# rs232-4ch.net
KiCad netlist of a schematic drawn in Altium Designer
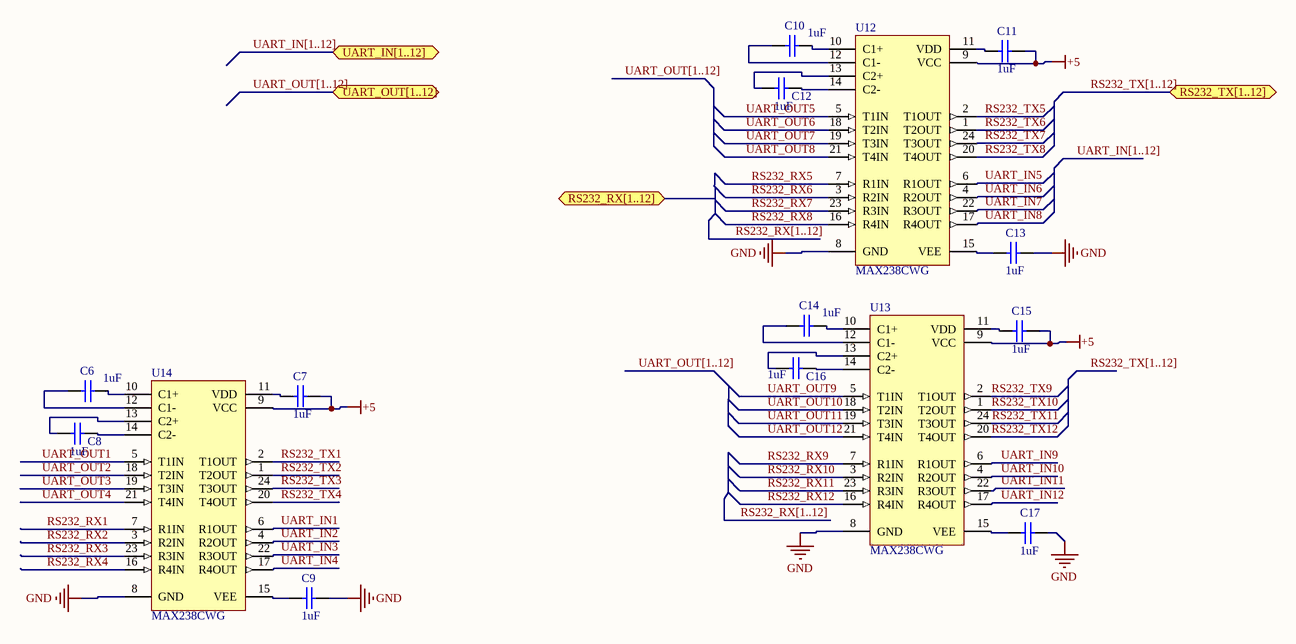
[diagram p0: rs232-4ch.SchDoc]

(export (version "E")
  (design (tool "Eeschema 10.0.6"))
  (components
    (comp (ref "C6")
      (value "1uF")
      (footprint "CAPC1608M")
      (description "Capacitor")
      (fields (field (name "Comment") "Cap") (field (name "PUBLISHER") "Altium Limited"))
      (libsource (lib "Miscellaneous Devices") (part "Cap"))
    )
    (comp (ref "C7")
      (value "1uF")
      (footprint "CAPC1608M")
      (description "Capacitor")
      (fields (field (name "Comment") "Cap") (field (name "PUBLISHER") "Altium Limited"))
      (libsource (lib "Miscellaneous Devices") (part "Cap"))
    )
    (comp (ref "C8")
      (value "1uF")
      (footprint "CAPC1608M")
      (description "Capacitor")
      (fields (field (name "Comment") "Cap") (field (name "PUBLISHER") "Altium Limited"))
      (libsource (lib "Miscellaneous Devices") (part "Cap"))
    )
    (comp (ref "C9")
      (value "1uF")
      (footprint "CAPC1608M")
      (description "Capacitor")
      (fields (field (name "Comment") "Cap") (field (name "PUBLISHER") "Altium Limited"))
      (libsource (lib "Miscellaneous Devices") (part "Cap"))
    )
    (comp (ref "C10")
      (value "1uF")
      (footprint "CAPC1608M")
      (description "Capacitor")
      (fields (field (name "Comment") "Cap") (field (name "PUBLISHER") "Altium Limited"))
      (libsource (lib "Miscellaneous Devices") (part "Cap"))
    )
    (comp (ref "C11")
      (value "1uF")
      (footprint "CAPC1608M")
      (description "Capacitor")
      (fields (field (name "Comment") "Cap") (field (name "PUBLISHER") "Altium Limited"))
      (libsource (lib "Miscellaneous Devices") (part "Cap"))
    )
    (comp (ref "C12")
      (value "1uF")
      (footprint "CAPC1608M")
      (description "Capacitor")
      (fields (field (name "Comment") "Cap") (field (name "PUBLISHER") "Altium Limited"))
      (libsource (lib "Miscellaneous Devices") (part "Cap"))
    )
    (comp (ref "C13")
      (value "1uF")
      (footprint "CAPC1608M")
      (description "Capacitor")
      (fields (field (name "Comment") "Cap") (field (name "PUBLISHER") "Altium Limited"))
      (libsource (lib "Miscellaneous Devices") (part "Cap"))
    )
    (comp (ref "C14")
      (value "1uF")
      (footprint "CAPC1608M")
      (description "Capacitor")
      (fields (field (name "Comment") "Cap") (field (name "PUBLISHER") "Altium Limited"))
      (libsource (lib "Miscellaneous Devices") (part "Cap"))
    )
    (comp (ref "C15")
      (value "1uF")
      (footprint "CAPC1608M")
      (description "Capacitor")
      (fields (field (name "Comment") "Cap") (field (name "PUBLISHER") "Altium Limited"))
      (libsource (lib "Miscellaneous Devices") (part "Cap"))
    )
    (comp (ref "C16")
      (value "1uF")
      (footprint "CAPC1608M")
      (description "Capacitor")
      (fields (field (name "Comment") "Cap") (field (name "PUBLISHER") "Altium Limited"))
      (libsource (lib "Miscellaneous Devices") (part "Cap"))
    )
    (comp (ref "C17")
      (value "1uF")
      (footprint "CAPC1608M")
      (description "Capacitor")
      (fields (field (name "Comment") "Cap") (field (name "PUBLISHER") "Altium Limited"))
      (libsource (lib "Miscellaneous Devices") (part "Cap"))
    )
    (comp (ref "U12")
      (value "MAX238CWG")
      (footprint "WSO24_N")
      (description "+5V Powered RS-232 Driver/Receiver")
      (fields (field (name "PUBLISHER") "Altium Limited"))
      (libsource (lib "Maxim Communication Transceiver") (part "MAX238CWG"))
    )
    (comp (ref "U13")
      (value "MAX238CWG")
      (footprint "WSO24_N")
      (description "+5V Powered RS-232 Driver/Receiver")
      (fields (field (name "PUBLISHER") "Altium Limited"))
      (libsource (lib "Maxim Communication Transceiver") (part "MAX238CWG"))
    )
    (comp (ref "U14")
      (value "MAX238CWG")
      (footprint "WSO24_N")
      (description "+5V Powered RS-232 Driver/Receiver")
      (fields (field (name "PUBLISHER") "Altium Limited"))
      (libsource (lib "Maxim Communication Transceiver") (part "MAX238CWG"))
    )
  )
  (nets
    (net (code "1") (name "+5") (class "Default")
      (node (ref "C11") (pin "1") (pinfunction "1_1") (pintype "passive"))
      (node (ref "C15") (pin "1") (pinfunction "1_1") (pintype "passive"))
      (node (ref "C7") (pin "1") (pinfunction "1_1") (pintype "passive"))
      (node (ref "U12") (pin "9") (pinfunction "VCC_9") (pintype "power_in"))
      (node (ref "U13") (pin "9") (pinfunction "VCC_9") (pintype "power_in"))
      (node (ref "U14") (pin "9") (pinfunction "VCC_9") (pintype "power_in"))
    )
    (net (code "2") (name "/RS232_RX1") (class "Default")
      (node (ref "U14") (pin "7") (pinfunction "R1IN_7") (pintype "input"))
    )
    (net (code "3") (name "/RS232_RX2") (class "Default")
      (node (ref "U14") (pin "3") (pinfunction "R2IN_3") (pintype "input"))
    )
    (net (code "4") (name "/RS232_RX3") (class "Default")
      (node (ref "U14") (pin "23") (pinfunction "R3IN_23") (pintype "input"))
    )
    (net (code "5") (name "/RS232_RX4") (class "Default")
      (node (ref "U14") (pin "16") (pinfunction "R4IN_16") (pintype "input"))
    )
    (net (code "6") (name "/RS232_RX5") (class "Default")
      (node (ref "U12") (pin "7") (pinfunction "R1IN_7") (pintype "input"))
    )
    (net (code "7") (name "/RS232_RX6") (class "Default")
      (node (ref "U12") (pin "3") (pinfunction "R2IN_3") (pintype "input"))
    )
    (net (code "8") (name "/RS232_RX7") (class "Default")
      (node (ref "U12") (pin "23") (pinfunction "R3IN_23") (pintype "input"))
    )
    (net (code "9") (name "/RS232_RX8") (class "Default")
      (node (ref "U12") (pin "16") (pinfunction "R4IN_16") (pintype "input"))
    )
    (net (code "10") (name "/RS232_RX9") (class "Default")
      (node (ref "U13") (pin "7") (pinfunction "R1IN_7") (pintype "input"))
    )
    (net (code "11") (name "/RS232_RX10") (class "Default")
      (node (ref "U13") (pin "3") (pinfunction "R2IN_3") (pintype "input"))
    )
    (net (code "12") (name "/RS232_RX11") (class "Default")
      (node (ref "U13") (pin "23") (pinfunction "R3IN_23") (pintype "input"))
    )
    (net (code "13") (name "/RS232_RX12") (class "Default")
      (node (ref "U13") (pin "16") (pinfunction "R4IN_16") (pintype "input"))
    )
    (net (code "15") (name "/RS232_TX1") (class "Default")
      (node (ref "U14") (pin "2") (pinfunction "T1OUT_2") (pintype "output"))
    )
    (net (code "16") (name "/RS232_TX2") (class "Default")
      (node (ref "U14") (pin "1") (pinfunction "T2OUT_1") (pintype "output"))
    )
    (net (code "17") (name "/RS232_TX3") (class "Default")
      (node (ref "U14") (pin "24") (pinfunction "T3OUT_24") (pintype "output"))
    )
    (net (code "18") (name "/RS232_TX4") (class "Default")
      (node (ref "U14") (pin "20") (pinfunction "T4OUT_20") (pintype "output"))
    )
    (net (code "19") (name "/RS232_TX5") (class "Default")
      (node (ref "U12") (pin "2") (pinfunction "T1OUT_2") (pintype "output"))
    )
    (net (code "20") (name "/RS232_TX6") (class "Default")
      (node (ref "U12") (pin "1") (pinfunction "T2OUT_1") (pintype "output"))
    )
    (net (code "21") (name "/RS232_TX7") (class "Default")
      (node (ref "U12") (pin "24") (pinfunction "T3OUT_24") (pintype "output"))
    )
    (net (code "22") (name "/RS232_TX8") (class "Default")
      (node (ref "U12") (pin "20") (pinfunction "T4OUT_20") (pintype "output"))
    )
    (net (code "23") (name "/RS232_TX9") (class "Default")
      (node (ref "U13") (pin "2") (pinfunction "T1OUT_2") (pintype "output"))
    )
    (net (code "24") (name "/RS232_TX10") (class "Default")
      (node (ref "U13") (pin "1") (pinfunction "T2OUT_1") (pintype "output"))
    )
    (net (code "25") (name "/RS232_TX11") (class "Default")
      (node (ref "U13") (pin "24") (pinfunction "T3OUT_24") (pintype "output"))
    )
    (net (code "26") (name "/RS232_TX12") (class "Default")
      (node (ref "U13") (pin "20") (pinfunction "T4OUT_20") (pintype "output"))
    )
    (net (code "28") (name "/UART_IN1") (class "Default")
      (node (ref "U14") (pin "6") (pinfunction "R1OUT_6") (pintype "output"))
    )
    (net (code "29") (name "/UART_IN2") (class "Default")
      (node (ref "U14") (pin "4") (pinfunction "R2OUT_4") (pintype "output"))
    )
    (net (code "30") (name "/UART_IN3") (class "Default")
      (node (ref "U14") (pin "22") (pinfunction "R3OUT_22") (pintype "output"))
    )
    (net (code "31") (name "/UART_IN4") (class "Default")
      (node (ref "U14") (pin "17") (pinfunction "R4OUT_17") (pintype "output"))
    )
    (net (code "32") (name "/UART_IN5") (class "Default")
      (node (ref "U12") (pin "6") (pinfunction "R1OUT_6") (pintype "output"))
    )
    (net (code "33") (name "/UART_IN6") (class "Default")
      (node (ref "U12") (pin "4") (pinfunction "R2OUT_4") (pintype "output"))
    )
    (net (code "34") (name "/UART_IN7") (class "Default")
      (node (ref "U12") (pin "22") (pinfunction "R3OUT_22") (pintype "output"))
    )
    (net (code "35") (name "/UART_IN8") (class "Default")
      (node (ref "U12") (pin "17") (pinfunction "R4OUT_17") (pintype "output"))
    )
    (net (code "36") (name "/UART_IN9") (class "Default")
      (node (ref "U13") (pin "6") (pinfunction "R1OUT_6") (pintype "output"))
    )
    (net (code "37") (name "/UART_IN10") (class "Default")
      (node (ref "U13") (pin "4") (pinfunction "R2OUT_4") (pintype "output"))
    )
    (net (code "38") (name "/UART_IN11") (class "Default")
      (node (ref "U13") (pin "22") (pinfunction "R3OUT_22") (pintype "output"))
    )
    (net (code "39") (name "/UART_IN12") (class "Default")
      (node (ref "U13") (pin "17") (pinfunction "R4OUT_17") (pintype "output"))
    )
    (net (code "41") (name "/UART_OUT1") (class "Default")
      (node (ref "U14") (pin "5") (pinfunction "T1IN_5") (pintype "input"))
    )
    (net (code "42") (name "/UART_OUT2") (class "Default")
      (node (ref "U14") (pin "18") (pinfunction "T2IN_18") (pintype "input"))
    )
    (net (code "43") (name "/UART_OUT3") (class "Default")
      (node (ref "U14") (pin "19") (pinfunction "T3IN_19") (pintype "input"))
    )
    (net (code "44") (name "/UART_OUT4") (class "Default")
      (node (ref "U14") (pin "21") (pinfunction "T4IN_21") (pintype "input"))
    )
    (net (code "45") (name "/UART_OUT5") (class "Default")
      (node (ref "U12") (pin "5") (pinfunction "T1IN_5") (pintype "input"))
    )
    (net (code "46") (name "/UART_OUT6") (class "Default")
      (node (ref "U12") (pin "18") (pinfunction "T2IN_18") (pintype "input"))
    )
    (net (code "47") (name "/UART_OUT7") (class "Default")
      (node (ref "U12") (pin "19") (pinfunction "T3IN_19") (pintype "input"))
    )
    (net (code "48") (name "/UART_OUT8") (class "Default")
      (node (ref "U12") (pin "21") (pinfunction "T4IN_21") (pintype "input"))
    )
    (net (code "49") (name "/UART_OUT9") (class "Default")
      (node (ref "U13") (pin "5") (pinfunction "T1IN_5") (pintype "input"))
    )
    (net (code "50") (name "/UART_OUT10") (class "Default")
      (node (ref "U13") (pin "18") (pinfunction "T2IN_18") (pintype "input"))
    )
    (net (code "51") (name "/UART_OUT11") (class "Default")
      (node (ref "U13") (pin "19") (pinfunction "T3IN_19") (pintype "input"))
    )
    (net (code "52") (name "/UART_OUT12") (class "Default")
      (node (ref "U13") (pin "21") (pinfunction "T4IN_21") (pintype "input"))
    )
    (net (code "54") (name "GND") (class "Default")
      (node (ref "C13") (pin "1") (pinfunction "1_1") (pintype "passive"))
      (node (ref "C17") (pin "1") (pinfunction "1_1") (pintype "passive"))
      (node (ref "C9") (pin "1") (pinfunction "1_1") (pintype "passive"))
      (node (ref "U12") (pin "8") (pinfunction "GND_8") (pintype "power_in"))
      (node (ref "U13") (pin "8") (pinfunction "GND_8") (pintype "power_in"))
      (node (ref "U14") (pin "8") (pinfunction "GND_8") (pintype "power_in"))
    )
    (net (code "55") (name "Net-(U12-C1+)") (class "Default")
      (node (ref "C10") (pin "1") (pinfunction "1_1") (pintype "passive"))
      (node (ref "U12") (pin "10") (pinfunction "C1+_10") (pintype "passive"))
    )
    (net (code "56") (name "Net-(U12-C1-)") (class "Default")
      (node (ref "C10") (pin "2") (pinfunction "2_2") (pintype "passive"))
      (node (ref "U12") (pin "12") (pinfunction "C1-_12") (pintype "passive"))
    )
    (net (code "57") (name "Net-(U12-C2+)") (class "Default")
      (node (ref "C12") (pin "2") (pinfunction "2_2") (pintype "passive"))
      (node (ref "U12") (pin "13") (pinfunction "C2+_13") (pintype "passive"))
    )
    (net (code "58") (name "Net-(U12-C2-)") (class "Default")
      (node (ref "C12") (pin "1") (pinfunction "1_1") (pintype "passive"))
      (node (ref "U12") (pin "14") (pinfunction "C2-_14") (pintype "passive"))
    )
    (net (code "59") (name "Net-(U12-VDD)") (class "Default")
      (node (ref "C11") (pin "2") (pinfunction "2_2") (pintype "passive"))
      (node (ref "U12") (pin "11") (pinfunction "VDD_11") (pintype "power_in"))
    )
    (net (code "60") (name "Net-(U12-VEE)") (class "Default")
      (node (ref "C13") (pin "2") (pinfunction "2_2") (pintype "passive"))
      (node (ref "U12") (pin "15") (pinfunction "VEE_15") (pintype "power_in"))
    )
    (net (code "61") (name "Net-(U13-C1+)") (class "Default")
      (node (ref "C14") (pin "1") (pinfunction "1_1") (pintype "passive"))
      (node (ref "U13") (pin "10") (pinfunction "C1+_10") (pintype "passive"))
    )
    (net (code "62") (name "Net-(U13-C1-)") (class "Default")
      (node (ref "C14") (pin "2") (pinfunction "2_2") (pintype "passive"))
      (node (ref "U13") (pin "12") (pinfunction "C1-_12") (pintype "passive"))
    )
    (net (code "63") (name "Net-(U13-C2+)") (class "Default")
      (node (ref "C16") (pin "2") (pinfunction "2_2") (pintype "passive"))
      (node (ref "U13") (pin "13") (pinfunction "C2+_13") (pintype "passive"))
    )
    (net (code "64") (name "Net-(U13-C2-)") (class "Default")
      (node (ref "C16") (pin "1") (pinfunction "1_1") (pintype "passive"))
      (node (ref "U13") (pin "14") (pinfunction "C2-_14") (pintype "passive"))
    )
    (net (code "65") (name "Net-(U13-VDD)") (class "Default")
      (node (ref "C15") (pin "2") (pinfunction "2_2") (pintype "passive"))
      (node (ref "U13") (pin "11") (pinfunction "VDD_11") (pintype "power_in"))
    )
    (net (code "66") (name "Net-(U13-VEE)") (class "Default")
      (node (ref "C17") (pin "2") (pinfunction "2_2") (pintype "passive"))
      (node (ref "U13") (pin "15") (pinfunction "VEE_15") (pintype "power_in"))
    )
    (net (code "67") (name "Net-(U14-C1+)") (class "Default")
      (node (ref "C6") (pin "1") (pinfunction "1_1") (pintype "passive"))
      (node (ref "U14") (pin "10") (pinfunction "C1+_10") (pintype "passive"))
    )
    (net (code "68") (name "Net-(U14-C1-)") (class "Default")
      (node (ref "C6") (pin "2") (pinfunction "2_2") (pintype "passive"))
      (node (ref "U14") (pin "12") (pinfunction "C1-_12") (pintype "passive"))
    )
    (net (code "69") (name "Net-(U14-C2+)") (class "Default")
      (node (ref "C8") (pin "2") (pinfunction "2_2") (pintype "passive"))
      (node (ref "U14") (pin "13") (pinfunction "C2+_13") (pintype "passive"))
    )
    (net (code "70") (name "Net-(U14-C2-)") (class "Default")
      (node (ref "C8") (pin "1") (pinfunction "1_1") (pintype "passive"))
      (node (ref "U14") (pin "14") (pinfunction "C2-_14") (pintype "passive"))
    )
    (net (code "71") (name "Net-(U14-VDD)") (class "Default")
      (node (ref "C7") (pin "2") (pinfunction "2_2") (pintype "passive"))
      (node (ref "U14") (pin "11") (pinfunction "VDD_11") (pintype "power_in"))
    )
    (net (code "72") (name "Net-(U14-VEE)") (class "Default")
      (node (ref "C9") (pin "2") (pinfunction "2_2") (pintype "passive"))
      (node (ref "U14") (pin "15") (pinfunction "VEE_15") (pintype "power_in"))
    )
  )
)
